# Virtual_Ground.net
KiCad netlist of a schematic drawn in Altium Designer
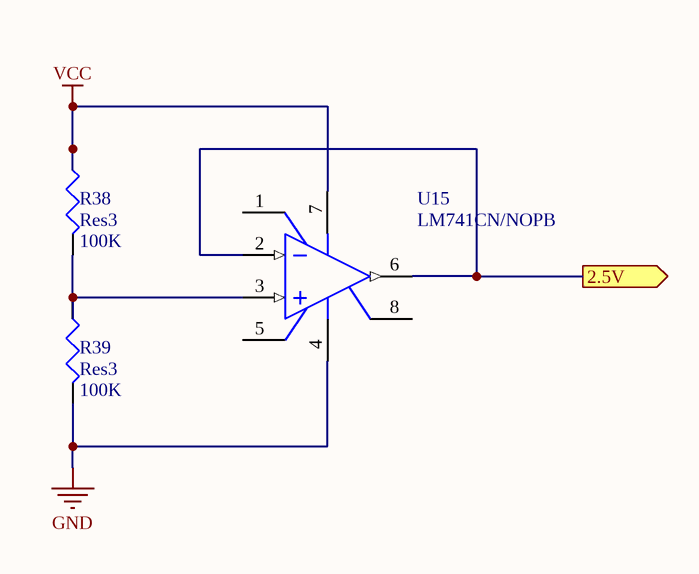
[diagram p0: Virtual_Ground.SchDoc]

(export (version "E")
  (design (tool "Eeschema 10.0.6"))
  (components
    (comp (ref "R38")
      (value "Res3")
      (footprint "J1-0603")
      (description "Resistor")
      (fields (field (name "ALTIUM_VALUE") "100K") (field (name "PUBLISHER") "Altium Limited"))
      (libsource (lib "Miscellaneous Devices") (part "Res3"))
    )
    (comp (ref "R39")
      (value "Res3")
      (footprint "J1-0603")
      (description "Resistor")
      (fields (field (name "ALTIUM_VALUE") "100K") (field (name "PUBLISHER") "Altium Limited"))
      (libsource (lib "Miscellaneous Devices") (part "Res3"))
    )
    (comp (ref "U15")
      (value "LM741CN/NOPB")
      (footprint "P0008A")
      (description "Operational Amplifier, 8-pin MDIP, Pb-Free")
      (fields (field (name "MANUFACTURER") "Texas Instruments"))
      (libsource (lib "Altium Content Vault") (part "AMP-OPA-LM741-8"))
    )
  )
  (nets
    (net (code "1") (name "/2.5V") (class "Default")
      (node (ref "U15") (pin "2") (pinfunction "IN-_2") (pintype "input"))
      (node (ref "U15") (pin "6") (pinfunction "OUT_6") (pintype "output"))
    )
    (net (code "2") (name "GND") (class "Default")
      (node (ref "R39") (pin "1") (pinfunction "1_1") (pintype "passive"))
      (node (ref "U15") (pin "4") (pinfunction "V-_4") (pintype "power_in"))
    )
    (net (code "3") (name "Net-(U15-IN+)") (class "Default")
      (node (ref "R38") (pin "1") (pinfunction "1_1") (pintype "passive"))
      (node (ref "R39") (pin "2") (pinfunction "2_2") (pintype "passive"))
      (node (ref "U15") (pin "3") (pinfunction "IN+_3") (pintype "input"))
    )
    (net (code "4") (name "VCC") (class "Default")
      (node (ref "R38") (pin "2") (pinfunction "2_2") (pintype "passive"))
      (node (ref "U15") (pin "7") (pinfunction "V+_7") (pintype "power_in"))
    )
    (net (code "5") (name "unconnected-(U15-NC-Pad8)") (class "Default")
      (node (ref "U15") (pin "8") (pinfunction "NC_8") (pintype "passive"))
    )
    (net (code "6") (name "unconnected-(U15-OFS_NULL-Pad1)") (class "Default")
      (node (ref "U15") (pin "1") (pinfunction "OFS_NULL_1") (pintype "passive"))
    )
    (net (code "7") (name "unconnected-(U15-OFS_NULL-Pad5)") (class "Default")
      (node (ref "U15") (pin "5") (pinfunction "OFS_NULL_5") (pintype "passive"))
    )
  )
)
